# Modem.net
KiCad netlist of a schematic drawn in Altium Designer
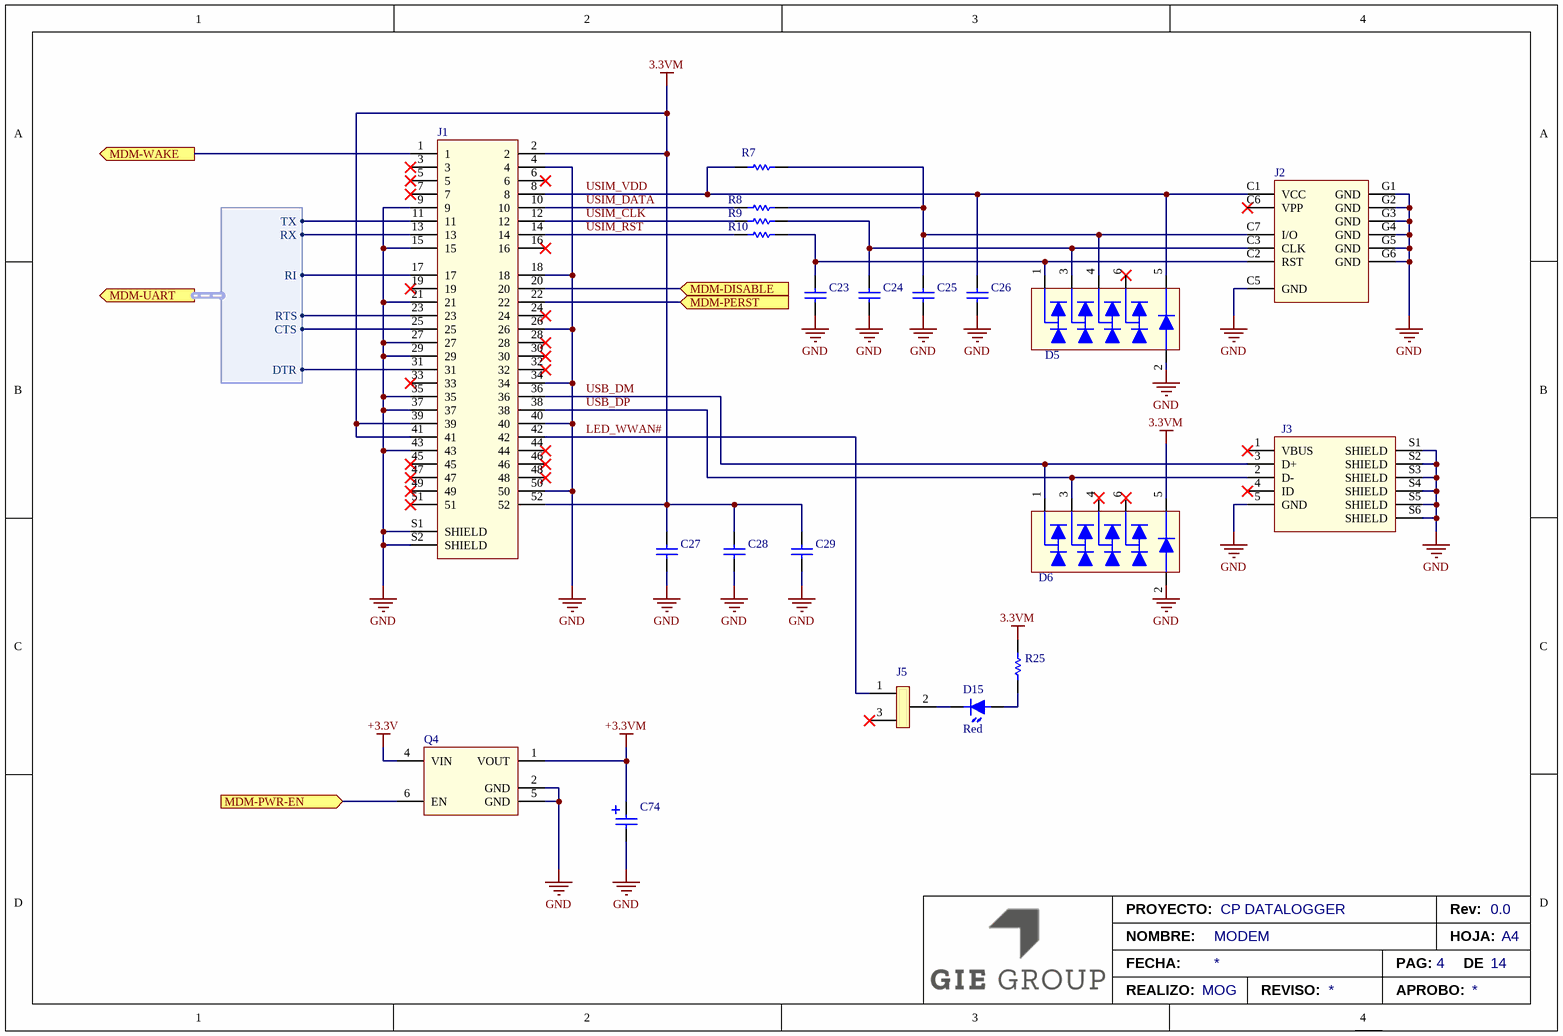
[diagram p0: Modem.SchDoc]

(export (version "E")
  (design (tool "Eeschema 10.0.6"))
  (components
    (comp (ref "C23")
      (value "C0603C330F3GAC7867")
      (footprint "CAP-0603")
      (description "CAP CER 33 pF 25V C0G 0603")
      (fields (field (name "MANUFACTURER") "Kemet") (field (name "TOLERANCE") "1%"))
      (libsource (lib "Kemet") (part "C0603C330F3GAC7867"))
    )
    (comp (ref "C24")
      (value "C0603C330F3GAC7867")
      (footprint "CAP-0603")
      (description "CAP CER 33 pF 25V C0G 0603")
      (fields (field (name "MANUFACTURER") "Kemet") (field (name "TOLERANCE") "1%"))
      (libsource (lib "Kemet") (part "C0603C330F3GAC7867"))
    )
    (comp (ref "C25")
      (value "C0603C330F3GAC7867")
      (footprint "CAP-0603")
      (description "CAP CER 33 pF 25V C0G 0603")
      (fields (field (name "MANUFACTURER") "Kemet") (field (name "TOLERANCE") "1%"))
      (libsource (lib "Kemet") (part "C0603C330F3GAC7867"))
    )
    (comp (ref "C26")
      (value "C0603C330F3GAC7867")
      (footprint "CAP-0603")
      (description "CAP CER 33 pF 25V C0G 0603")
      (fields (field (name "MANUFACTURER") "Kemet") (field (name "TOLERANCE") "1%"))
      (libsource (lib "Kemet") (part "C0603C330F3GAC7867"))
    )
    (comp (ref "C27")
      (value "C0603C104K5RACAUTO")
      (footprint "CAP-0603")
      (description "CAP CER 0.1uF 50V X7R 0603")
      (fields (field (name "MANUFACTURER") "Kemet") (field (name "TOLERANCE") "10%"))
      (libsource (lib "Kemet") (part "C0603C104K5RACAUTO"))
    )
    (comp (ref "C28")
      (value "C0603C330F3GAC7867")
      (footprint "CAP-0603")
      (description "CAP CER 33 pF 25V C0G 0603")
      (fields (field (name "MANUFACTURER") "Kemet") (field (name "TOLERANCE") "1%"))
      (libsource (lib "Kemet") (part "C0603C330F3GAC7867"))
    )
    (comp (ref "C29")
      (value "C0603C100K3GAC7867")
      (footprint "CAP-0603")
      (description "CAP CER 10 pF 25V C0G 0603")
      (fields (field (name "MANUFACTURER") "Kemet") (field (name "TOLERANCE") "10%"))
      (libsource (lib "Kemet") (part "C0603C100K3GAC7867"))
    )
    (comp (ref "C74")
      (value "EEE-FK0J471P")
      (footprint "CAP_ALUM_SIZE_F")
      (description "CAP ALUM 470UF 20% 6.3V SMD")
      (fields (field (name "MANUFACTURER") "Panasonic"))
      (libsource (lib "Panasonic") (part "EEE-FK0J471P"))
    )
    (comp (ref "D5")
      (value "~")
      (footprint "TSSOP6")
      (description "TVS DIODE 3.3VWM 10VC 4CH SC74")
      (fields (field (name "MANUFACTURER") "OnSemiconductor"))
      (libsource (lib "OnSemiconductors") (part "CM1213A-04SO"))
    )
    (comp (ref "D6")
      (value "~")
      (footprint "TSSOP6")
      (description "TVS DIODE 3.3VWM 10VC 4CH SC74")
      (fields (field (name "MANUFACTURER") "OnSemiconductor"))
      (libsource (lib "OnSemiconductors") (part "CM1213A-04SO"))
    )
    (comp (ref "D15")
      (value "LTST-C170KRKT")
      (footprint "0805 - LED")
      (description "LED RED CLEAR 0805 SMD")
      (fields (field (name "MANUFACTURER") "Lite-On Inc") (field (name "COLOR") "Red"))
      (libsource (lib "LiteOn") (part "LTST-C170KRKT"))
    )
    (comp (ref "J1")
      (value "0679100002")
      (footprint "MOLEX-679100002")
      (description "Connector Mini PCI Express 52POS - Quectel modem")
      (fields (field (name "MANUFACTURER") "Molex"))
      (libsource (lib "Molex") (part "Molex 0679100002"))
    )
    (comp (ref "J2")
      (value "~")
      (footprint "MOLEX-786463001")
      (description "6 Position Card Connector Micro SIM Surface Mount, Right Angle Gold")
      (libsource (lib "Molex") (part "786463001"))
    )
    (comp (ref "J3")
      (value "473460001")
      (footprint "MOLEX-473460001")
      (description "USB Connectors MICRO USB B RECPT BTTM MOUNT ASSY")
      (fields (field (name "MANUFACTURER") "Molex"))
      (libsource (lib "Molex") (part "473460001"))
    )
    (comp (ref "J5")
      (value "PRPC003SAAN-RC")
      (footprint "PIN3")
      (description "CONN HEADER .100\" SNGL STR 3POS")
      (fields (field (name "MANUFACTURER") "Sullins Connector Solutions"))
      (libsource (lib "Sullins") (part "PRPC003SAAN-RC"))
    )
    (comp (ref "Q4")
      (value "~")
      (footprint "TSSOP6")
      (fields (field (name "MANUFACTURER") "Microchip"))
      (libsource (lib "Microchip") (part "MIC94092YC6-TR"))
    )
    (comp (ref "R7")
      (value "RC0603FR-0715KL")
      (footprint "RES-0603")
      (description "RES SMD 15.0K OHM 1% 1/10W 0603")
      (fields (field (name "TOLERANCE") "1%") (field (name "MANUFACTURER") "Yageo"))
      (libsource (lib "Yageo") (part "RC0603FR-0715KL"))
    )
    (comp (ref "R8")
      (value "RC0603FR-0722RL")
      (footprint "RES-0603")
      (description "RES SMD 22 OHM 1% 1/10W 0603")
      (fields (field (name "TOLERANCE") "1%") (field (name "MANUFACTURER") "Yageo"))
      (libsource (lib "Yageo") (part "RC0603FR-0722RL"))
    )
    (comp (ref "R9")
      (value "RC0603FR-0722RL")
      (footprint "RES-0603")
      (description "RES SMD 22 OHM 1% 1/10W 0603")
      (fields (field (name "TOLERANCE") "1%") (field (name "MANUFACTURER") "Yageo"))
      (libsource (lib "Yageo") (part "RC0603FR-0722RL"))
    )
    (comp (ref "R10")
      (value "RC0603FR-0722RL")
      (footprint "RES-0603")
      (description "RES SMD 22 OHM 1% 1/10W 0603")
      (fields (field (name "TOLERANCE") "1%") (field (name "MANUFACTURER") "Yageo"))
      (libsource (lib "Yageo") (part "RC0603FR-0722RL"))
    )
    (comp (ref "R25")
      (value "RC0805FR-07100KL")
      (footprint "RES-0603")
      (description "RES SMD 105 OHM 1% 1/8W 0805")
      (fields (field (name "TOLERANCE") "1%") (field (name "MANUFACTURER") "Yageo"))
      (libsource (lib "Yageo") (part "RC0805FR-07105RL"))
    )
  )
  (nets
    (net (code "2") (name "+3.3V") (class "Default")
      (node (ref "Q4") (pin "4") (pinfunction "VIN_4") (pintype "passive"))
    )
    (net (code "3") (name "+3.3VM") (class "Default")
      (node (ref "C74") (pin "1") (pinfunction "1_1") (pintype "passive"))
      (node (ref "Q4") (pin "1") (pinfunction "VOUT_1") (pintype "passive"))
    )
    (net (code "4") (name "/CTS") (class "Default")
      (node (ref "J1") (pin "25") (pinfunction "25_25") (pintype "passive"))
    )
    (net (code "5") (name "/DTR") (class "Default")
      (node (ref "J1") (pin "31") (pinfunction "31_31") (pintype "passive"))
    )
    (net (code "6") (name "/LED_WWAN#") (class "Default")
      (node (ref "J1") (pin "42") (pinfunction "42_42") (pintype "passive"))
      (node (ref "J5") (pin "1") (pinfunction "1_1") (pintype "passive"))
    )
    (net (code "7") (name "/MDM-DISABLE") (class "Default")
      (node (ref "J1") (pin "20") (pinfunction "20_20") (pintype "passive"))
    )
    (net (code "8") (name "/MDM-PERST") (class "Default")
      (node (ref "J1") (pin "22") (pinfunction "22_22") (pintype "passive"))
    )
    (net (code "9") (name "/MDM-PWR-EN") (class "Default")
      (node (ref "Q4") (pin "6") (pinfunction "EN_6") (pintype "passive"))
    )
    (net (code "10") (name "/MDM-WAKE") (class "Default")
      (node (ref "J1") (pin "1") (pinfunction "1_1") (pintype "passive"))
    )
    (net (code "11") (name "/RI") (class "Default")
      (node (ref "J1") (pin "17") (pinfunction "17_17") (pintype "passive"))
    )
    (net (code "12") (name "/RTS") (class "Default")
      (node (ref "J1") (pin "23") (pinfunction "23_23") (pintype "passive"))
    )
    (net (code "13") (name "/RX") (class "Default")
      (node (ref "J1") (pin "13") (pinfunction "13_13") (pintype "passive"))
    )
    (net (code "14") (name "/TX") (class "Default")
      (node (ref "J1") (pin "11") (pinfunction "11_11") (pintype "passive"))
    )
    (net (code "15") (name "/USB_DM") (class "Default")
      (node (ref "D6") (pin "1") (pinfunction "1_1") (pintype "passive"))
      (node (ref "J1") (pin "36") (pinfunction "36_36") (pintype "passive"))
      (node (ref "J3") (pin "3") (pinfunction "D+_3") (pintype "power_in"))
    )
    (net (code "16") (name "/USB_DP") (class "Default")
      (node (ref "D6") (pin "3") (pinfunction "3_3") (pintype "passive"))
      (node (ref "J1") (pin "38") (pinfunction "38_38") (pintype "passive"))
      (node (ref "J3") (pin "2") (pinfunction "D-_2") (pintype "power_in"))
    )
    (net (code "17") (name "/USIM_CLK") (class "Default")
      (node (ref "J1") (pin "12") (pinfunction "12_12") (pintype "passive"))
      (node (ref "R9") (pin "1") (pinfunction "1_1") (pintype "passive"))
    )
    (net (code "18") (name "/USIM_DATA") (class "Default")
      (node (ref "J1") (pin "10") (pinfunction "10_10") (pintype "passive"))
      (node (ref "R8") (pin "1") (pinfunction "1_1") (pintype "passive"))
    )
    (net (code "19") (name "/USIM_RST") (class "Default")
      (node (ref "J1") (pin "14") (pinfunction "14_14") (pintype "passive"))
      (node (ref "R10") (pin "1") (pinfunction "1_1") (pintype "passive"))
    )
    (net (code "20") (name "/USIM_VDD") (class "Default")
      (node (ref "C26") (pin "2") (pinfunction "2_2") (pintype "passive"))
      (node (ref "D5") (pin "5") (pinfunction "5_5") (pintype "passive"))
      (node (ref "J1") (pin "8") (pinfunction "8_8") (pintype "passive"))
      (node (ref "J2") (pin "C1") (pinfunction "VCC_C1") (pintype "power_in"))
      (node (ref "R7") (pin "1") (pinfunction "1_1") (pintype "passive"))
    )
    (net (code "22") (name "3.3VM") (class "Default")
      (node (ref "C27") (pin "2") (pinfunction "2_2") (pintype "passive"))
      (node (ref "C28") (pin "2") (pinfunction "2_2") (pintype "passive"))
      (node (ref "C29") (pin "2") (pinfunction "2_2") (pintype "passive"))
      (node (ref "D6") (pin "5") (pinfunction "5_5") (pintype "passive"))
      (node (ref "J1") (pin "2") (pinfunction "2_2") (pintype "passive"))
      (node (ref "J1") (pin "39") (pinfunction "39_39") (pintype "passive"))
      (node (ref "J1") (pin "41") (pinfunction "41_41") (pintype "passive"))
      (node (ref "J1") (pin "52") (pinfunction "52_52") (pintype "passive"))
      (node (ref "R25") (pin "2") (pinfunction "2_2") (pintype "passive"))
    )
    (net (code "23") (name "GND") (class "Default")
      (node (ref "C23") (pin "1") (pinfunction "1_1") (pintype "passive"))
      (node (ref "C24") (pin "1") (pinfunction "1_1") (pintype "passive"))
      (node (ref "C25") (pin "1") (pinfunction "1_1") (pintype "passive"))
      (node (ref "C26") (pin "1") (pinfunction "1_1") (pintype "passive"))
      (node (ref "C27") (pin "1") (pinfunction "1_1") (pintype "passive"))
      (node (ref "C28") (pin "1") (pinfunction "1_1") (pintype "passive"))
      (node (ref "C29") (pin "1") (pinfunction "1_1") (pintype "passive"))
      (node (ref "C74") (pin "2") (pinfunction "2_2") (pintype "passive"))
      (node (ref "D5") (pin "2") (pinfunction "2_2") (pintype "passive"))
      (node (ref "D6") (pin "2") (pinfunction "2_2") (pintype "passive"))
      (node (ref "J1") (pin "15") (pinfunction "15_15") (pintype "passive"))
      (node (ref "J1") (pin "18") (pinfunction "18_18") (pintype "passive"))
      (node (ref "J1") (pin "21") (pinfunction "21_21") (pintype "passive"))
      (node (ref "J1") (pin "26") (pinfunction "26_26") (pintype "passive"))
      (node (ref "J1") (pin "27") (pinfunction "27_27") (pintype "passive"))
      (node (ref "J1") (pin "29") (pinfunction "29_29") (pintype "passive"))
      (node (ref "J1") (pin "34") (pinfunction "34_34") (pintype "passive"))
      (node (ref "J1") (pin "35") (pinfunction "35_35") (pintype "passive"))
      (node (ref "J1") (pin "37") (pinfunction "37_37") (pintype "passive"))
      (node (ref "J1") (pin "4") (pinfunction "4_4") (pintype "passive"))
      (node (ref "J1") (pin "40") (pinfunction "40_40") (pintype "passive"))
      (node (ref "J1") (pin "43") (pinfunction "43_43") (pintype "passive"))
      (node (ref "J1") (pin "50") (pinfunction "50_50") (pintype "passive"))
      (node (ref "J1") (pin "9") (pinfunction "9_9") (pintype "passive"))
      (node (ref "J1") (pin "S1") (pinfunction "SHIELD_S1") (pintype "passive"))
      (node (ref "J1") (pin "S2") (pinfunction "SHIELD_S2") (pintype "passive"))
      (node (ref "J2") (pin "C5") (pinfunction "GND_C5") (pintype "power_in"))
      (node (ref "J2") (pin "G1") (pinfunction "GND_G1") (pintype "power_in"))
      (node (ref "J2") (pin "G2") (pinfunction "GND_G2") (pintype "power_in"))
      (node (ref "J2") (pin "G3") (pinfunction "GND_G3") (pintype "power_in"))
      (node (ref "J2") (pin "G4") (pinfunction "GND_G4") (pintype "power_in"))
      (node (ref "J2") (pin "G5") (pinfunction "GND_G5") (pintype "power_in"))
      (node (ref "J2") (pin "G6") (pinfunction "GND_G6") (pintype "power_in"))
      (node (ref "J3") (pin "5") (pinfunction "GND_5") (pintype "power_in"))
      (node (ref "J3") (pin "S1") (pinfunction "SHIELD_S1") (pintype "passive"))
      (node (ref "J3") (pin "S2") (pinfunction "SHIELD_S2") (pintype "passive"))
      (node (ref "J3") (pin "S3") (pinfunction "SHIELD_S3") (pintype "passive"))
      (node (ref "J3") (pin "S4") (pinfunction "SHIELD_S4") (pintype "passive"))
      (node (ref "J3") (pin "S5") (pinfunction "SHIELD_S5") (pintype "passive"))
      (node (ref "J3") (pin "S6") (pinfunction "SHIELD_S6") (pintype "passive"))
      (node (ref "Q4") (pin "2") (pinfunction "GND_2") (pintype "passive"))
      (node (ref "Q4") (pin "5") (pinfunction "GND_5") (pintype "passive"))
    )
    (net (code "24") (name "Net-(D15-A)") (class "Default")
      (node (ref "D15") (pin "1") (pinfunction "A_1") (pintype "passive"))
      (node (ref "R25") (pin "1") (pinfunction "1_1") (pintype "passive"))
    )
    (net (code "25") (name "Net-(D15-K)") (class "Default")
      (node (ref "D15") (pin "2") (pinfunction "K_2") (pintype "passive"))
      (node (ref "J5") (pin "2") (pinfunction "2_2") (pintype "passive"))
    )
    (net (code "26") (name "Net-(J2-CLK)") (class "Default")
      (node (ref "C24") (pin "2") (pinfunction "2_2") (pintype "passive"))
      (node (ref "D5") (pin "3") (pinfunction "3_3") (pintype "passive"))
      (node (ref "J2") (pin "C3") (pinfunction "CLK_C3") (pintype "power_in"))
      (node (ref "R9") (pin "2") (pinfunction "2_2") (pintype "passive"))
    )
    (net (code "27") (name "Net-(J2-I{slash}O)") (class "Default")
      (node (ref "C25") (pin "2") (pinfunction "2_2") (pintype "passive"))
      (node (ref "D5") (pin "4") (pinfunction "4_4") (pintype "passive"))
      (node (ref "J2") (pin "C7") (pinfunction "I/O_C7") (pintype "power_in"))
      (node (ref "R7") (pin "2") (pinfunction "2_2") (pintype "passive"))
      (node (ref "R8") (pin "2") (pinfunction "2_2") (pintype "passive"))
    )
    (net (code "28") (name "Net-(J2-RST)") (class "Default")
      (node (ref "C23") (pin "2") (pinfunction "2_2") (pintype "passive"))
      (node (ref "D5") (pin "1") (pinfunction "1_1") (pintype "passive"))
      (node (ref "J2") (pin "C2") (pinfunction "RST_C2") (pintype "power_in"))
      (node (ref "R10") (pin "2") (pinfunction "2_2") (pintype "passive"))
    )
    (net (code "29") (name "unconnected-(D5-Pad6)") (class "Default")
      (node (ref "D5") (pin "6") (pinfunction "6_6") (pintype "passive+no_connect"))
    )
    (net (code "30") (name "unconnected-(D6-Pad4)") (class "Default")
      (node (ref "D6") (pin "4") (pinfunction "4_4") (pintype "passive+no_connect"))
    )
    (net (code "31") (name "unconnected-(D6-Pad6)") (class "Default")
      (node (ref "D6") (pin "6") (pinfunction "6_6") (pintype "passive+no_connect"))
    )
    (net (code "32") (name "unconnected-(J1-Pad3)") (class "Default")
      (node (ref "J1") (pin "3") (pinfunction "3_3") (pintype "passive+no_connect"))
    )
    (net (code "33") (name "unconnected-(J1-Pad5)") (class "Default")
      (node (ref "J1") (pin "5") (pinfunction "5_5") (pintype "passive+no_connect"))
    )
    (net (code "34") (name "unconnected-(J1-Pad6)") (class "Default")
      (node (ref "J1") (pin "6") (pinfunction "6_6") (pintype "passive+no_connect"))
    )
    (net (code "35") (name "unconnected-(J1-Pad7)") (class "Default")
      (node (ref "J1") (pin "7") (pinfunction "7_7") (pintype "passive+no_connect"))
    )
    (net (code "36") (name "unconnected-(J1-Pad16)") (class "Default")
      (node (ref "J1") (pin "16") (pinfunction "16_16") (pintype "passive+no_connect"))
    )
    (net (code "37") (name "unconnected-(J1-Pad19)") (class "Default")
      (node (ref "J1") (pin "19") (pinfunction "19_19") (pintype "passive+no_connect"))
    )
    (net (code "38") (name "unconnected-(J1-Pad24)") (class "Default")
      (node (ref "J1") (pin "24") (pinfunction "24_24") (pintype "passive+no_connect"))
    )
    (net (code "39") (name "unconnected-(J1-Pad28)") (class "Default")
      (node (ref "J1") (pin "28") (pinfunction "28_28") (pintype "passive+no_connect"))
    )
    (net (code "40") (name "unconnected-(J1-Pad30)") (class "Default")
      (node (ref "J1") (pin "30") (pinfunction "30_30") (pintype "passive+no_connect"))
    )
    (net (code "41") (name "unconnected-(J1-Pad32)") (class "Default")
      (node (ref "J1") (pin "32") (pinfunction "32_32") (pintype "passive+no_connect"))
    )
    (net (code "42") (name "unconnected-(J1-Pad33)") (class "Default")
      (node (ref "J1") (pin "33") (pinfunction "33_33") (pintype "passive+no_connect"))
    )
    (net (code "43") (name "unconnected-(J1-Pad44)") (class "Default")
      (node (ref "J1") (pin "44") (pinfunction "44_44") (pintype "passive+no_connect"))
    )
    (net (code "44") (name "unconnected-(J1-Pad45)") (class "Default")
      (node (ref "J1") (pin "45") (pinfunction "45_45") (pintype "passive+no_connect"))
    )
    (net (code "45") (name "unconnected-(J1-Pad46)") (class "Default")
      (node (ref "J1") (pin "46") (pinfunction "46_46") (pintype "passive+no_connect"))
    )
    (net (code "46") (name "unconnected-(J1-Pad47)") (class "Default")
      (node (ref "J1") (pin "47") (pinfunction "47_47") (pintype "passive+no_connect"))
    )
    (net (code "47") (name "unconnected-(J1-Pad48)") (class "Default")
      (node (ref "J1") (pin "48") (pinfunction "48_48") (pintype "passive+no_connect"))
    )
    (net (code "48") (name "unconnected-(J1-Pad49)") (class "Default")
      (node (ref "J1") (pin "49") (pinfunction "49_49") (pintype "passive+no_connect"))
    )
    (net (code "49") (name "unconnected-(J1-Pad51)") (class "Default")
      (node (ref "J1") (pin "51") (pinfunction "51_51") (pintype "passive+no_connect"))
    )
    (net (code "50") (name "unconnected-(J2-VPP-PadC6)") (class "Default")
      (node (ref "J2") (pin "C6") (pinfunction "VPP_C6") (pintype "power_in+no_connect"))
    )
    (net (code "51") (name "unconnected-(J3-ID-Pad4)") (class "Default")
      (node (ref "J3") (pin "4") (pinfunction "ID_4") (pintype "power_in+no_connect"))
    )
    (net (code "52") (name "unconnected-(J3-VBUS-Pad1)") (class "Default")
      (node (ref "J3") (pin "1") (pinfunction "VBUS_1") (pintype "power_in+no_connect"))
    )
    (net (code "53") (name "unconnected-(J5-Pad3)") (class "Default")
      (node (ref "J5") (pin "3") (pinfunction "3_3") (pintype "passive+no_connect"))
    )
  )
)
